# Schametics.net
KiCad netlist of a schematic drawn in EAGLE
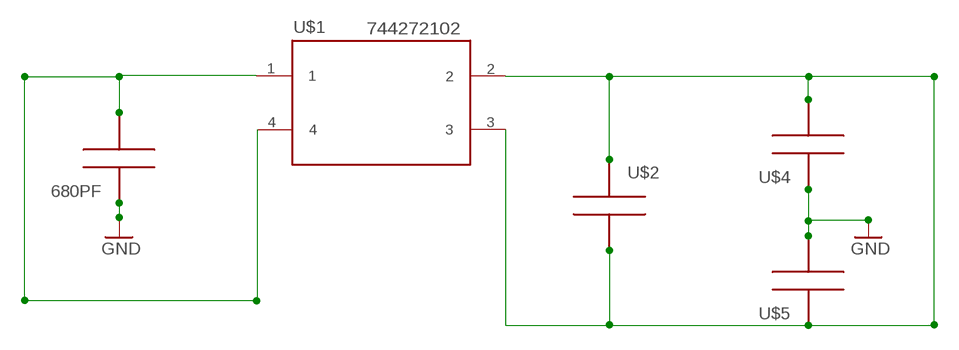
[diagram p0: schematic, sheet 1]

(export (version "E")
  (design (tool "Eeschema 10.0.6"))
  (components
    (comp (ref "680PF")
      (value "CAPA1206")
      (footprint "eagle-import:FGJGFN")
      (libsource (lib "eagle-import") (part "CAPA1206"))
    )
    (comp (ref "U$1")
      (value "CHOKE")
      (footprint "eagle-import:CHOKE")
      (libsource (lib "eagle-import") (part "CHOKE"))
    )
    (comp (ref "U$2")
      (value "CAPA1206")
      (footprint "eagle-import:FGJGFN")
      (libsource (lib "eagle-import") (part "CAPA1206"))
    )
    (comp (ref "U$4")
      (value "CAPA1206")
      (footprint "eagle-import:FGJGFN")
      (libsource (lib "eagle-import") (part "CAPA1206"))
    )
    (comp (ref "U$5")
      (value "CAPA1206")
      (footprint "eagle-import:FGJGFN")
      (libsource (lib "eagle-import") (part "CAPA1206"))
    )
  )
  (nets
    (net (code "1") (name "GND") (class "Default")
      (node (ref "680PF") (pin "2") (pinfunction "2_2") (pintype "passive"))
    )
    (net (code "2") (name "Net-(680PF-Pad1)") (class "Default")
      (node (ref "680PF") (pin "1") (pinfunction "1_1") (pintype "passive"))
      (node (ref "U$1") (pin "4") (pinfunction "4_4") (pintype "passive"))
    )
    (net (code "3") (name "Net-(U$1-Pad3)") (class "Default")
      (node (ref "U$1") (pin "3") (pinfunction "3_3") (pintype "passive"))
      (node (ref "U$4") (pin "1") (pinfunction "1_1") (pintype "passive"))
      (node (ref "U$5") (pin "2") (pinfunction "2_2") (pintype "passive"))
    )
    (net (code "4") (name "Net-(U$4-Pad2)") (class "Default")
      (node (ref "U$4") (pin "2") (pinfunction "2_2") (pintype "passive"))
      (node (ref "U$5") (pin "1") (pinfunction "1_1") (pintype "passive"))
    )
    (net (code "5") (name "unconnected-(U$1-Pad1)") (class "Default")
      (node (ref "U$1") (pin "1") (pinfunction "1_1") (pintype "passive"))
    )
    (net (code "6") (name "unconnected-(U$1-Pad2)") (class "Default")
      (node (ref "U$1") (pin "2") (pinfunction "2_2") (pintype "passive"))
    )
    (net (code "7") (name "unconnected-(U$2-Pad1)") (class "Default")
      (node (ref "U$2") (pin "1") (pinfunction "1_1") (pintype "passive"))
    )
    (net (code "8") (name "unconnected-(U$2-Pad2)") (class "Default")
      (node (ref "U$2") (pin "2") (pinfunction "2_2") (pintype "passive"))
    )
  )
)
